# Hardwiring.net
KiCad netlist of a schematic drawn in Altium Designer
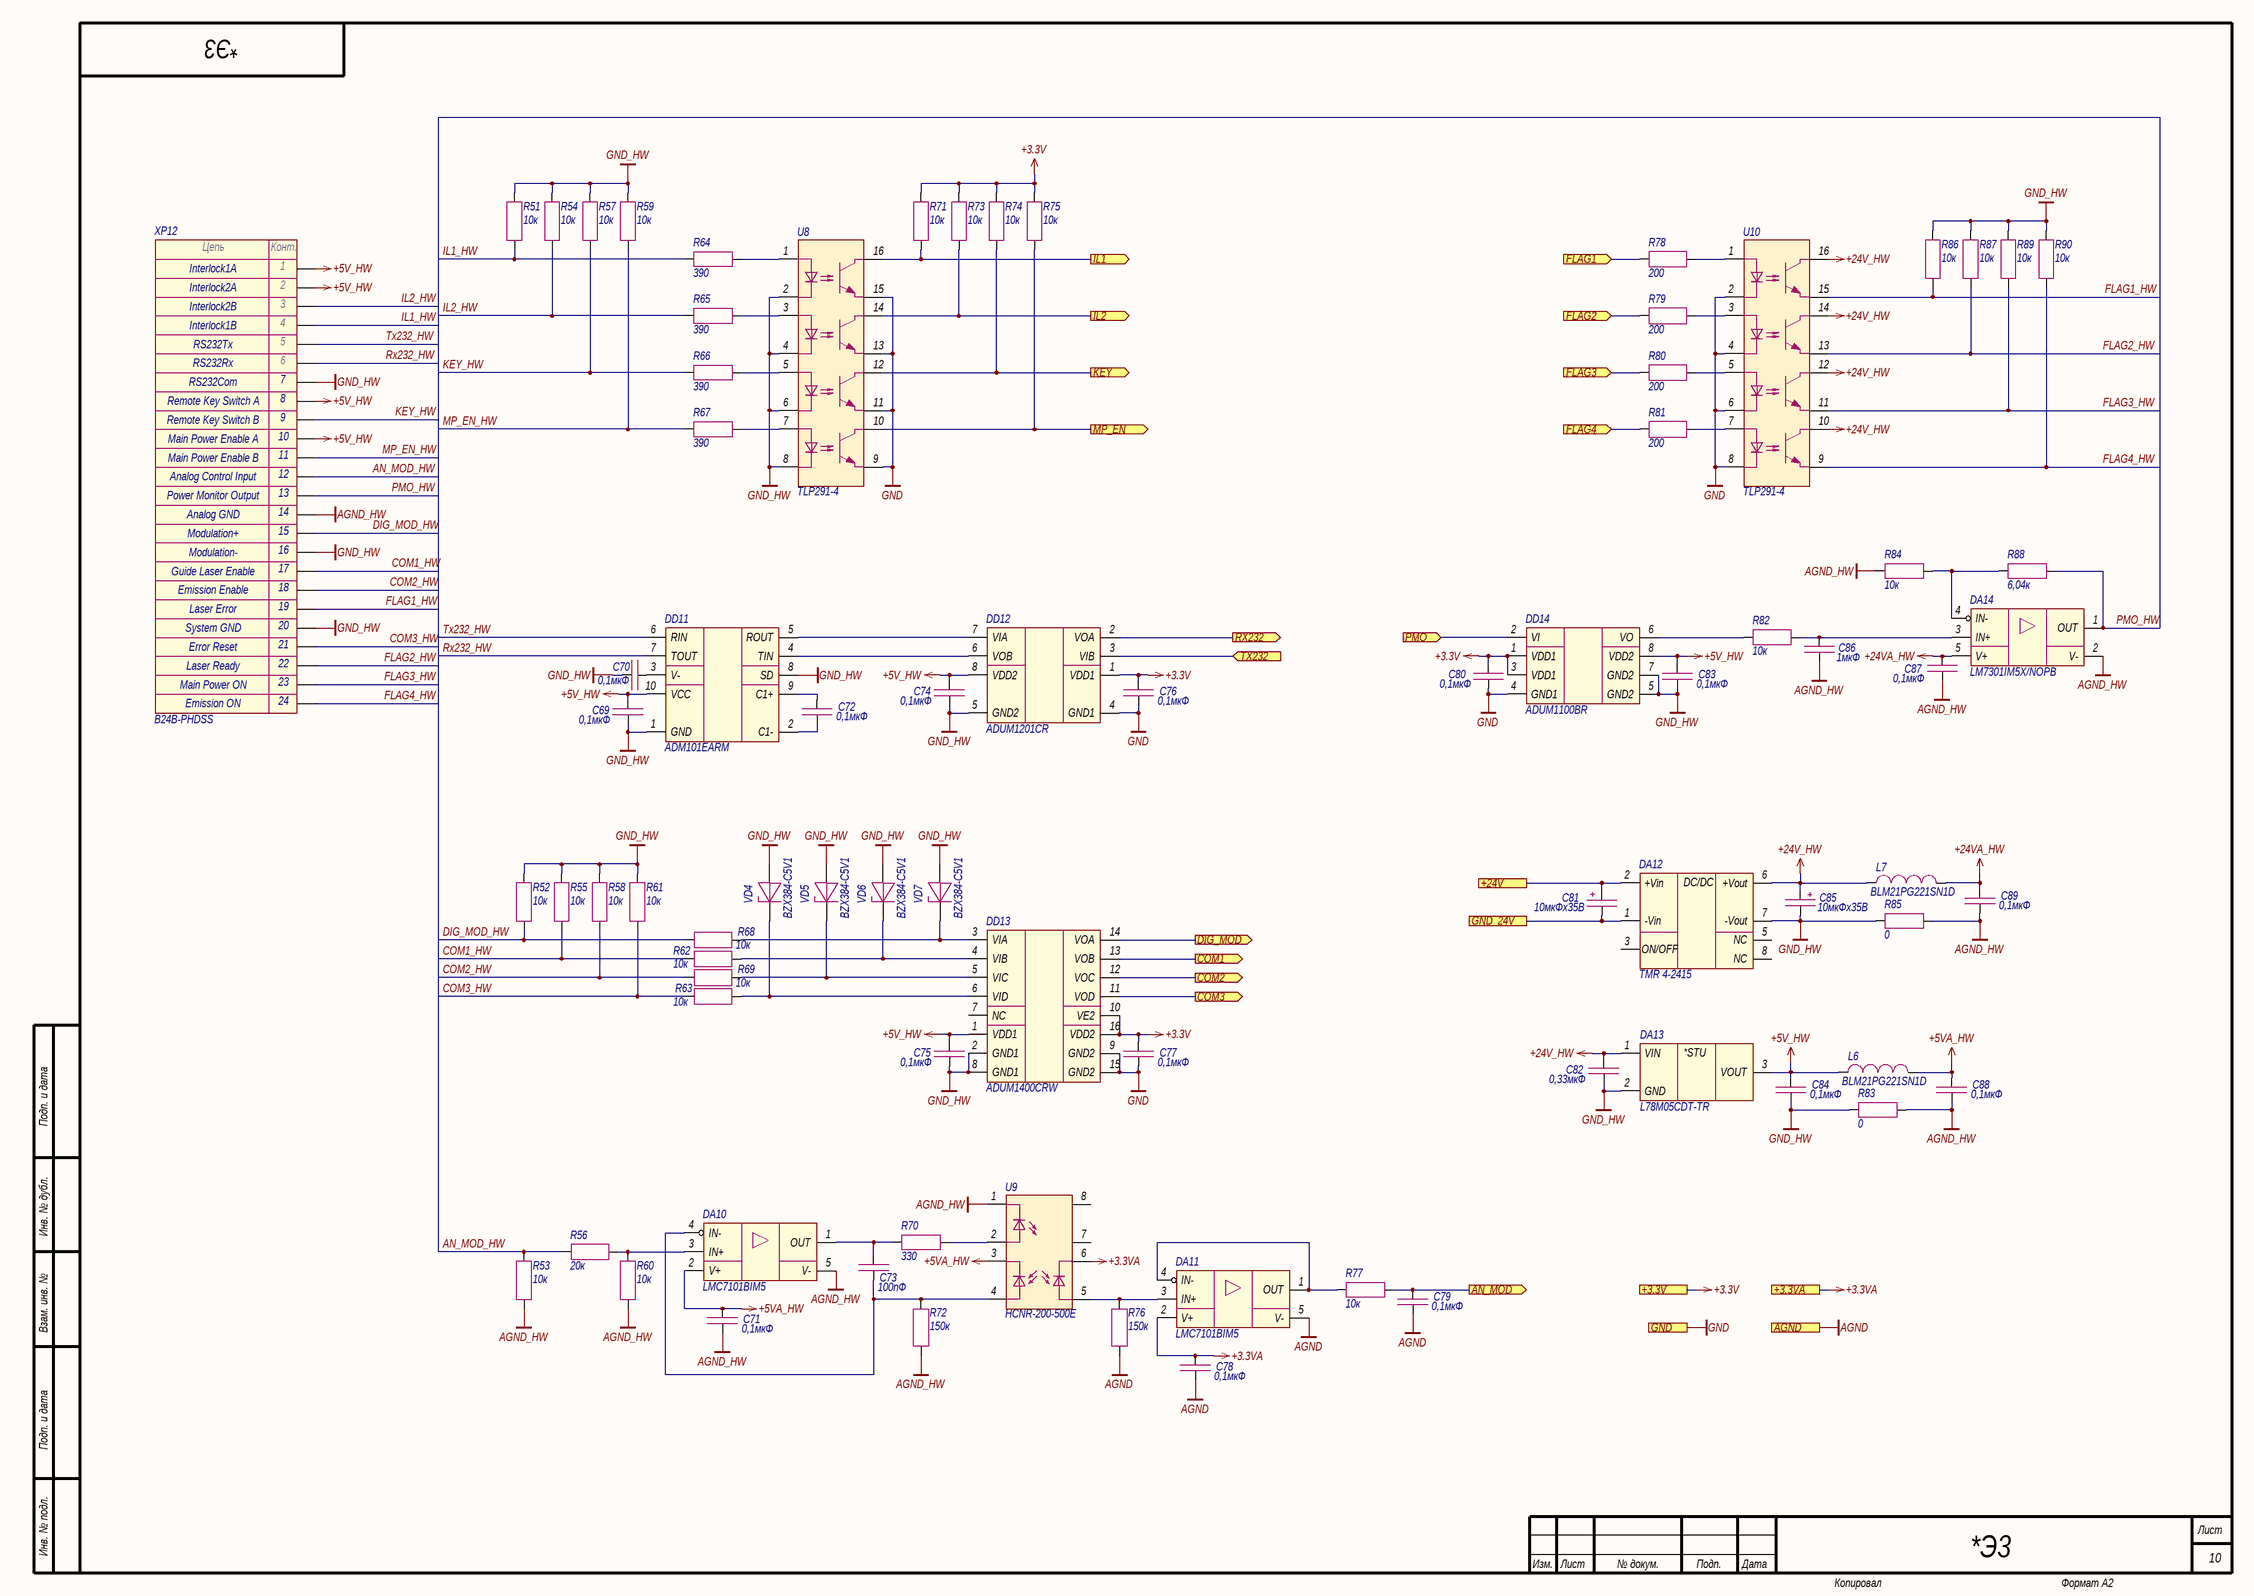
[diagram p0: Hardwiring.SchDoc]

(export (version "E")
  (design (tool "Eeschema 10.0.6"))
  (components
    (comp (ref "C69")
      (value "0,1мкФ")
      (footprint "Pcb_library:CAP_0603")
      (fields (field (name "MANUFACTURER") "Murata"))
      (libsource (lib "Schem_library") (part "Capacitor"))
    )
    (comp (ref "C70")
      (value "0,1мкФ")
      (footprint "Pcb_library:CAP_0603")
      (fields (field (name "MANUFACTURER") "Murata"))
      (libsource (lib "Schem_library") (part "Capacitor"))
    )
    (comp (ref "C71")
      (value "0,1мкФ")
      (footprint "Pcb_library:CAP_0603")
      (fields (field (name "MANUFACTURER") "Murata"))
      (libsource (lib "Schem_library") (part "Capacitor"))
    )
    (comp (ref "C72")
      (value "0,1мкФ")
      (footprint "Pcb_library:CAP_0603")
      (fields (field (name "MANUFACTURER") "Murata"))
      (libsource (lib "Schem_library") (part "Capacitor"))
    )
    (comp (ref "C73")
      (value "100пФ")
      (footprint "Pcb_library:CAP_0603")
      (fields (field (name "MANUFACTURER") "Murata"))
      (libsource (lib "Schem_library") (part "Capacitor"))
    )
    (comp (ref "C74")
      (value "0,1мкФ")
      (footprint "Pcb_library:CAP_0603")
      (fields (field (name "MANUFACTURER") "Murata"))
      (libsource (lib "Schem_library") (part "Capacitor"))
    )
    (comp (ref "C75")
      (value "0,1мкФ")
      (footprint "Pcb_library:CAP_0603")
      (fields (field (name "MANUFACTURER") "Murata"))
      (libsource (lib "Schem_library") (part "Capacitor"))
    )
    (comp (ref "C76")
      (value "0,1мкФ")
      (footprint "Pcb_library:CAP_0603")
      (fields (field (name "MANUFACTURER") "Murata"))
      (libsource (lib "Schem_library") (part "Capacitor"))
    )
    (comp (ref "C77")
      (value "0,1мкФ")
      (footprint "Pcb_library:CAP_0603")
      (fields (field (name "MANUFACTURER") "Murata"))
      (libsource (lib "Schem_library") (part "Capacitor"))
    )
    (comp (ref "C78")
      (value "0,1мкФ")
      (footprint "Pcb_library:CAP_0603")
      (fields (field (name "MANUFACTURER") "Murata"))
      (libsource (lib "Schem_library") (part "Capacitor"))
    )
    (comp (ref "C79")
      (value "0,1мкФ")
      (footprint "Pcb_library:CAP_0603")
      (fields (field (name "MANUFACTURER") "Murata"))
      (libsource (lib "Schem_library") (part "Capacitor"))
    )
    (comp (ref "C80")
      (value "0,1мкФ")
      (footprint "Pcb_library:CAP_0603")
      (fields (field (name "MANUFACTURER") "Murata"))
      (libsource (lib "Schem_library") (part "Capacitor"))
    )
    (comp (ref "C81")
      (value "10мкФх35B")
      (footprint "Pcb_library:CAP_C")
      (libsource (lib "Schem_library") (part "Capacitor_Polar"))
    )
    (comp (ref "C82")
      (value "0,33мкФ")
      (footprint "Pcb_library:CAP_0805")
      (fields (field (name "MANUFACTURER") "Murata"))
      (libsource (lib "Schem_library") (part "Capacitor"))
    )
    (comp (ref "C83")
      (value "0,1мкФ")
      (footprint "Pcb_library:CAP_0603")
      (fields (field (name "MANUFACTURER") "Murata"))
      (libsource (lib "Schem_library") (part "Capacitor"))
    )
    (comp (ref "C84")
      (value "0,1мкФ")
      (footprint "Pcb_library:CAP_0603")
      (fields (field (name "MANUFACTURER") "Murata"))
      (libsource (lib "Schem_library") (part "Capacitor"))
    )
    (comp (ref "C85")
      (value "10мкФх35B")
      (footprint "Pcb_library:CAP_C")
      (libsource (lib "Schem_library") (part "Capacitor_Polar"))
    )
    (comp (ref "C86")
      (value "1мкФ")
      (footprint "Pcb_library:CAP_0603")
      (fields (field (name "MANUFACTURER") "Murata"))
      (libsource (lib "Schem_library") (part "Capacitor"))
    )
    (comp (ref "C87")
      (value "0,1мкФ")
      (footprint "Pcb_library:CAP_0603")
      (fields (field (name "MANUFACTURER") "Murata"))
      (libsource (lib "Schem_library") (part "Capacitor"))
    )
    (comp (ref "C88")
      (value "0,1мкФ")
      (footprint "Pcb_library:CAP_0603")
      (fields (field (name "MANUFACTURER") "Murata"))
      (libsource (lib "Schem_library") (part "Capacitor"))
    )
    (comp (ref "C89")
      (value "0,1мкФ")
      (footprint "Pcb_library:CAP_0603")
      (fields (field (name "MANUFACTURER") "Murata"))
      (libsource (lib "Schem_library") (part "Capacitor"))
    )
    (comp (ref "DA10")
      (value "LMC7101BIM5")
      (footprint "Pcb_library:SOT-23-5")
      (fields (field (name "MANUFACTURER") "Texas Instruments"))
      (libsource (lib "Schem_library") (part "LMC7101"))
    )
    (comp (ref "DA11")
      (value "LMC7101BIM5")
      (footprint "Pcb_library:SOT-23-5")
      (fields (field (name "MANUFACTURER") "Texas Instruments"))
      (libsource (lib "Schem_library") (part "LMC7101"))
    )
    (comp (ref "DA12")
      (value "TMR 4-2415")
      (footprint "Pcb_library:TMR4 (SIP-8)")
      (fields (field (name "MANUFACTURER") "Traco Power"))
      (libsource (lib "Schem_library") (part "TMR4"))
    )
    (comp (ref "DA13")
      (value "L78M05CDT-TR")
      (footprint "Pcb_library:TO-252")
      (fields (field (name "MANUFACTURER") "STMicroelectronics"))
      (libsource (lib "Schem_library") (part "L78M"))
    )
    (comp (ref "DA14")
      (value "LM7301IM5X/NOPB")
      (footprint "Pcb_library:SOT-23-5")
      (fields (field (name "MANUFACTURER") "Texas Instruments"))
      (libsource (lib "Schem_library") (part "LM7301IM5"))
    )
    (comp (ref "DD11")
      (value "ADM101EARM")
      (footprint "Pcb_library:MSOP-10")
      (fields (field (name "MANUFACTURER") "Analog Devices"))
      (libsource (lib "Schem_library") (part "ADM101EARM"))
    )
    (comp (ref "DD12")
      (value "ADUM1201CR")
      (footprint "Pcb_library:SOIC-8")
      (fields (field (name "MANUFACTURER") "Analog Devices"))
      (libsource (lib "Schem_library") (part "ADUM1201"))
    )
    (comp (ref "DD13")
      (value "ADUM1400CRW")
      (footprint "Pcb_library:SOIC-16W")
      (fields (field (name "MANUFACTURER") "Analog Devices"))
      (libsource (lib "Schem_library") (part "ADUM1400"))
    )
    (comp (ref "DD14")
      (value "ADUM1100BR")
      (footprint "Pcb_library:SOIC-8")
      (fields (field (name "MANUFACTURER") "Analog Devices"))
      (libsource (lib "Schem_library") (part "ADUM1100"))
    )
    (comp (ref "L6")
      (value "BLM21PG221SN1D")
      (footprint "Pcb_library:IND_0805")
      (fields (field (name "MANUFACTURER") "Murata"))
      (libsource (lib "Schem_library") (part "Inductor"))
    )
    (comp (ref "L7")
      (value "BLM21PG221SN1D")
      (footprint "Pcb_library:IND_0805")
      (fields (field (name "MANUFACTURER") "Murata"))
      (libsource (lib "Schem_library") (part "Inductor"))
    )
    (comp (ref "R51")
      (value "10к")
      (footprint "Pcb_library:RES_0603")
      (fields (field (name "MANUFACTURER") "Yageo"))
      (libsource (lib "Schem_library") (part "Resistor"))
    )
    (comp (ref "R52")
      (value "10к")
      (footprint "Pcb_library:RES_0603")
      (fields (field (name "MANUFACTURER") "Yageo"))
      (libsource (lib "Schem_library") (part "Resistor"))
    )
    (comp (ref "R53")
      (value "10к")
      (footprint "Pcb_library:RES_0603")
      (fields (field (name "MANUFACTURER") "Yageo"))
      (libsource (lib "Schem_library") (part "Resistor"))
    )
    (comp (ref "R54")
      (value "10к")
      (footprint "Pcb_library:RES_0603")
      (fields (field (name "MANUFACTURER") "Yageo"))
      (libsource (lib "Schem_library") (part "Resistor"))
    )
    (comp (ref "R55")
      (value "10к")
      (footprint "Pcb_library:RES_0603")
      (fields (field (name "MANUFACTURER") "Yageo"))
      (libsource (lib "Schem_library") (part "Resistor"))
    )
    (comp (ref "R56")
      (value "20к")
      (footprint "Pcb_library:RES_0603")
      (fields (field (name "MANUFACTURER") "Yageo"))
      (libsource (lib "Schem_library") (part "Resistor"))
    )
    (comp (ref "R57")
      (value "10к")
      (footprint "Pcb_library:RES_0603")
      (fields (field (name "MANUFACTURER") "Yageo"))
      (libsource (lib "Schem_library") (part "Resistor"))
    )
    (comp (ref "R58")
      (value "10к")
      (footprint "Pcb_library:RES_0603")
      (fields (field (name "MANUFACTURER") "Yageo"))
      (libsource (lib "Schem_library") (part "Resistor"))
    )
    (comp (ref "R59")
      (value "10к")
      (footprint "Pcb_library:RES_0603")
      (fields (field (name "MANUFACTURER") "Yageo"))
      (libsource (lib "Schem_library") (part "Resistor"))
    )
    (comp (ref "R60")
      (value "10к")
      (footprint "Pcb_library:RES_0603")
      (fields (field (name "MANUFACTURER") "Yageo"))
      (libsource (lib "Schem_library") (part "Resistor"))
    )
    (comp (ref "R61")
      (value "10к")
      (footprint "Pcb_library:RES_0603")
      (fields (field (name "MANUFACTURER") "Yageo"))
      (libsource (lib "Schem_library") (part "Resistor"))
    )
    (comp (ref "R62")
      (value "10к")
      (footprint "Pcb_library:RES_0603")
      (fields (field (name "MANUFACTURER") "Yageo"))
      (libsource (lib "Schem_library") (part "Resistor"))
    )
    (comp (ref "R63")
      (value "10к")
      (footprint "Pcb_library:RES_0603")
      (fields (field (name "MANUFACTURER") "Yageo"))
      (libsource (lib "Schem_library") (part "Resistor"))
    )
    (comp (ref "R64")
      (value "390")
      (footprint "Pcb_library:RES_0603")
      (fields (field (name "MANUFACTURER") "Yageo"))
      (libsource (lib "Schem_library") (part "Resistor"))
    )
    (comp (ref "R65")
      (value "390")
      (footprint "Pcb_library:RES_0603")
      (fields (field (name "MANUFACTURER") "Yageo"))
      (libsource (lib "Schem_library") (part "Resistor"))
    )
    (comp (ref "R66")
      (value "390")
      (footprint "Pcb_library:RES_0603")
      (fields (field (name "MANUFACTURER") "Yageo"))
      (libsource (lib "Schem_library") (part "Resistor"))
    )
    (comp (ref "R67")
      (value "390")
      (footprint "Pcb_library:RES_0603")
      (fields (field (name "MANUFACTURER") "Yageo"))
      (libsource (lib "Schem_library") (part "Resistor"))
    )
    (comp (ref "R68")
      (value "10к")
      (footprint "Pcb_library:RES_0603")
      (fields (field (name "MANUFACTURER") "Yageo"))
      (libsource (lib "Schem_library") (part "Resistor"))
    )
    (comp (ref "R69")
      (value "10к")
      (footprint "Pcb_library:RES_0603")
      (fields (field (name "MANUFACTURER") "Yageo"))
      (libsource (lib "Schem_library") (part "Resistor"))
    )
    (comp (ref "R70")
      (value "330")
      (footprint "Pcb_library:RES_0603")
      (fields (field (name "MANUFACTURER") "Yageo"))
      (libsource (lib "Schem_library") (part "Resistor"))
    )
    (comp (ref "R71")
      (value "10к")
      (footprint "Pcb_library:RES_0603")
      (fields (field (name "MANUFACTURER") "Yageo"))
      (libsource (lib "Schem_library") (part "Resistor"))
    )
    (comp (ref "R72")
      (value "150к")
      (footprint "Pcb_library:RES_0603")
      (fields (field (name "MANUFACTURER") "Yageo"))
      (libsource (lib "Schem_library") (part "Resistor"))
    )
    (comp (ref "R73")
      (value "10к")
      (footprint "Pcb_library:RES_0603")
      (fields (field (name "MANUFACTURER") "Yageo"))
      (libsource (lib "Schem_library") (part "Resistor"))
    )
    (comp (ref "R74")
      (value "10к")
      (footprint "Pcb_library:RES_0603")
      (fields (field (name "MANUFACTURER") "Yageo"))
      (libsource (lib "Schem_library") (part "Resistor"))
    )
    (comp (ref "R75")
      (value "10к")
      (footprint "Pcb_library:RES_0603")
      (fields (field (name "MANUFACTURER") "Yageo"))
      (libsource (lib "Schem_library") (part "Resistor"))
    )
    (comp (ref "R76")
      (value "150к")
      (footprint "Pcb_library:RES_0603")
      (fields (field (name "MANUFACTURER") "Yageo"))
      (libsource (lib "Schem_library") (part "Resistor"))
    )
    (comp (ref "R77")
      (value "10к")
      (footprint "Pcb_library:RES_0603")
      (fields (field (name "MANUFACTURER") "Yageo"))
      (libsource (lib "Schem_library") (part "Resistor"))
    )
    (comp (ref "R78")
      (value "200")
      (footprint "Pcb_library:RES_0603")
      (fields (field (name "MANUFACTURER") "Yageo"))
      (libsource (lib "Schem_library") (part "Resistor"))
    )
    (comp (ref "R79")
      (value "200")
      (footprint "Pcb_library:RES_0603")
      (fields (field (name "MANUFACTURER") "Yageo"))
      (libsource (lib "Schem_library") (part "Resistor"))
    )
    (comp (ref "R80")
      (value "200")
      (footprint "Pcb_library:RES_0603")
      (fields (field (name "MANUFACTURER") "Yageo"))
      (libsource (lib "Schem_library") (part "Resistor"))
    )
    (comp (ref "R81")
      (value "200")
      (footprint "Pcb_library:RES_0603")
      (fields (field (name "MANUFACTURER") "Yageo"))
      (libsource (lib "Schem_library") (part "Resistor"))
    )
    (comp (ref "R82")
      (value "10к")
      (footprint "Pcb_library:RES_0603")
      (fields (field (name "MANUFACTURER") "Yageo"))
      (libsource (lib "Schem_library") (part "Resistor"))
    )
    (comp (ref "R83")
      (value "0")
      (footprint "Pcb_library:RES_0805")
      (fields (field (name "MANUFACTURER") "Yageo"))
      (libsource (lib "Schem_library") (part "Resistor"))
    )
    (comp (ref "R84")
      (value "10к")
      (footprint "Pcb_library:RES_0603")
      (fields (field (name "MANUFACTURER") "Yageo"))
      (libsource (lib "Schem_library") (part "Resistor"))
    )
    (comp (ref "R85")
      (value "0")
      (footprint "Pcb_library:RES_0805")
      (fields (field (name "MANUFACTURER") "Yageo"))
      (libsource (lib "Schem_library") (part "Resistor"))
    )
    (comp (ref "R86")
      (value "10к")
      (footprint "Pcb_library:RES_0603")
      (fields (field (name "MANUFACTURER") "Yageo"))
      (libsource (lib "Schem_library") (part "Resistor"))
    )
    (comp (ref "R87")
      (value "10к")
      (footprint "Pcb_library:RES_0603")
      (fields (field (name "MANUFACTURER") "Yageo"))
      (libsource (lib "Schem_library") (part "Resistor"))
    )
    (comp (ref "R88")
      (value "6,04к")
      (footprint "Pcb_library:RES_0603")
      (fields (field (name "MANUFACTURER") "Yageo"))
      (libsource (lib "Schem_library") (part "Resistor"))
    )
    (comp (ref "R89")
      (value "10к")
      (footprint "Pcb_library:RES_0603")
      (fields (field (name "MANUFACTURER") "Yageo"))
      (libsource (lib "Schem_library") (part "Resistor"))
    )
    (comp (ref "R90")
      (value "10к")
      (footprint "Pcb_library:RES_0603")
      (fields (field (name "MANUFACTURER") "Yageo"))
      (libsource (lib "Schem_library") (part "Resistor"))
    )
    (comp (ref "U8")
      (value "TLP291-4")
      (footprint "Pcb_library:SOP-16")
      (fields (field (name "MANUFACTURER") "Toshiba"))
      (libsource (lib "Schem_library") (part "TLP281-4"))
    )
    (comp (ref "U9")
      (value "HCNR-200-500E")
      (footprint "Pcb_library:HCNR200")
      (fields (field (name "MANUFACTURER") "Avago"))
      (libsource (lib "Schem_library") (part "HCNR200"))
    )
    (comp (ref "U10")
      (value "TLP291-4")
      (footprint "Pcb_library:SOP-16")
      (fields (field (name "MANUFACTURER") "Toshiba"))
      (libsource (lib "Schem_library") (part "TLP281-4"))
    )
    (comp (ref "VD4")
      (value "BZX384-C5V1")
      (footprint "Pcb_library:SOD-323")
      (fields (field (name "MANUFACTURER") "Nexperia"))
      (libsource (lib "Schem_library") (part "Diode_Zener"))
    )
    (comp (ref "VD5")
      (value "BZX384-C5V1")
      (footprint "Pcb_library:SOD-323")
      (fields (field (name "MANUFACTURER") "Nexperia"))
      (libsource (lib "Schem_library") (part "Diode_Zener"))
    )
    (comp (ref "VD6")
      (value "BZX384-C5V1")
      (footprint "Pcb_library:SOD-323")
      (fields (field (name "MANUFACTURER") "Nexperia"))
      (libsource (lib "Schem_library") (part "Diode_Zener"))
    )
    (comp (ref "VD7")
      (value "BZX384-C5V1")
      (footprint "Pcb_library:SOD-323")
      (fields (field (name "MANUFACTURER") "Nexperia"))
      (libsource (lib "Schem_library") (part "Diode_Zener"))
    )
    (comp (ref "XP12")
      (value "B24B-PHDSS")
      (footprint "Pcb_library:B24B-PHDSS")
      (fields (field (name "MANUFACTURER") "JST"))
      (libsource (lib "Schem_library") (part "Connector-24"))
    )
  )
  (nets
    (net (code "1") (name "+3.3V") (class "Default")
      (node (ref "C76") (pin "1") (pinfunction "1_1") (pintype "passive"))
      (node (ref "C77") (pin "1") (pinfunction "1_1") (pintype "passive"))
      (node (ref "C80") (pin "1") (pinfunction "1_1") (pintype "passive"))
      (node (ref "DD12") (pin "1") (pinfunction "VDD1_1") (pintype "passive"))
      (node (ref "DD13") (pin "10") (pinfunction "VE2_10") (pintype "passive"))
      (node (ref "DD13") (pin "16") (pinfunction "VDD2_16") (pintype "passive"))
      (node (ref "DD14") (pin "1") (pinfunction "VDD1_1") (pintype "passive"))
      (node (ref "DD14") (pin "3") (pinfunction "VDD1_3") (pintype "passive"))
      (node (ref "R71") (pin "1") (pinfunction "1_1") (pintype "passive"))
      (node (ref "R73") (pin "1") (pinfunction "1_1") (pintype "passive"))
      (node (ref "R74") (pin "1") (pinfunction "1_1") (pintype "passive"))
      (node (ref "R75") (pin "1") (pinfunction "1_1") (pintype "passive"))
    )
    (net (code "2") (name "+3.3VA") (class "Default")
      (node (ref "C78") (pin "1") (pinfunction "1_1") (pintype "passive"))
      (node (ref "DA11") (pin "2") (pinfunction "V+_2") (pintype "passive"))
      (node (ref "U9") (pin "6") (pintype "passive"))
    )
    (net (code "3") (name "+5VA_HW") (class "Default")
      (node (ref "C71") (pin "1") (pinfunction "1_1") (pintype "passive"))
      (node (ref "C88") (pin "1") (pinfunction "1_1") (pintype "passive"))
      (node (ref "DA10") (pin "2") (pinfunction "V+_2") (pintype "passive"))
      (node (ref "L6") (pin "2") (pinfunction "2_2") (pintype "passive"))
      (node (ref "U9") (pin "3") (pintype "passive"))
    )
    (net (code "4") (name "+5V_HW") (class "Default")
      (node (ref "C69") (pin "1") (pinfunction "1_1") (pintype "passive"))
      (node (ref "C74") (pin "1") (pinfunction "1_1") (pintype "passive"))
      (node (ref "C75") (pin "1") (pinfunction "1_1") (pintype "passive"))
      (node (ref "C83") (pin "1") (pinfunction "1_1") (pintype "passive"))
      (node (ref "C84") (pin "1") (pinfunction "1_1") (pintype "passive"))
      (node (ref "DA13") (pin "3") (pinfunction "VOUT_3") (pintype "passive"))
      (node (ref "DD11") (pin "10") (pinfunction "VCC_10") (pintype "passive"))
      (node (ref "DD12") (pin "8") (pinfunction "VDD2_8") (pintype "passive"))
      (node (ref "DD13") (pin "1") (pinfunction "VDD1_1") (pintype "passive"))
      (node (ref "DD14") (pin "8") (pinfunction "VDD2_8") (pintype "passive"))
      (node (ref "L6") (pin "1") (pinfunction "1_1") (pintype "passive"))
      (node (ref "XP12") (pin "1") (pintype "passive"))
      (node (ref "XP12") (pin "10") (pintype "passive"))
      (node (ref "XP12") (pin "2") (pintype "passive"))
      (node (ref "XP12") (pin "8") (pintype "passive"))
    )
    (net (code "5") (name "+24VA_HW") (class "Default")
      (node (ref "C87") (pin "1") (pinfunction "1_1") (pintype "passive"))
      (node (ref "C89") (pin "1") (pinfunction "1_1") (pintype "passive"))
      (node (ref "DA14") (pin "5") (pinfunction "V+_5") (pintype "passive"))
      (node (ref "L7") (pin "2") (pinfunction "2_2") (pintype "passive"))
    )
    (net (code "6") (name "+24V_HW") (class "Default")
      (node (ref "C82") (pin "2") (pinfunction "2_2") (pintype "passive"))
      (node (ref "C85") (pin "1") (pinfunction "1_1") (pintype "passive"))
      (node (ref "DA12") (pin "6") (pinfunction "+Vout_6") (pintype "passive"))
      (node (ref "DA13") (pin "1") (pinfunction "VIN_1") (pintype "passive"))
      (node (ref "L7") (pin "1") (pinfunction "1_1") (pintype "passive"))
      (node (ref "U10") (pin "10") (pintype "passive"))
      (node (ref "U10") (pin "12") (pintype "passive"))
      (node (ref "U10") (pin "14") (pintype "passive"))
      (node (ref "U10") (pin "16") (pintype "passive"))
    )
    (net (code "7") (name "/+24V") (class "Default")
      (node (ref "C81") (pin "1") (pinfunction "1_1") (pintype "passive"))
      (node (ref "DA12") (pin "2") (pinfunction "+Vin_2") (pintype "passive"))
    )
    (net (code "8") (name "/AN_MOD") (class "Default")
      (node (ref "C79") (pin "1") (pinfunction "1_1") (pintype "passive"))
      (node (ref "R77") (pin "2") (pinfunction "2_2") (pintype "passive"))
    )
    (net (code "9") (name "/AN_MOD_HW") (class "Default")
      (node (ref "R53") (pin "1") (pinfunction "1_1") (pintype "passive"))
      (node (ref "R56") (pin "1") (pinfunction "1_1") (pintype "passive"))
      (node (ref "XP12") (pin "12") (pintype "passive"))
    )
    (net (code "10") (name "/COM1") (class "Default")
      (node (ref "DD13") (pin "13") (pinfunction "VOB_13") (pintype "passive"))
    )
    (net (code "11") (name "/COM1_HW") (class "Default")
      (node (ref "R55") (pin "2") (pinfunction "2_2") (pintype "passive"))
      (node (ref "R62") (pin "1") (pinfunction "1_1") (pintype "passive"))
      (node (ref "XP12") (pin "17") (pintype "passive"))
    )
    (net (code "12") (name "/COM2") (class "Default")
      (node (ref "DD13") (pin "12") (pinfunction "VOC_12") (pintype "passive"))
    )
    (net (code "13") (name "/COM2_HW") (class "Default")
      (node (ref "R58") (pin "2") (pinfunction "2_2") (pintype "passive"))
      (node (ref "R69") (pin "1") (pinfunction "1_1") (pintype "passive"))
      (node (ref "XP12") (pin "18") (pintype "passive"))
    )
    (net (code "14") (name "/COM3") (class "Default")
      (node (ref "DD13") (pin "11") (pinfunction "VOD_11") (pintype "passive"))
    )
    (net (code "15") (name "/COM3_HW") (class "Default")
      (node (ref "R61") (pin "2") (pinfunction "2_2") (pintype "passive"))
      (node (ref "R63") (pin "1") (pinfunction "1_1") (pintype "passive"))
      (node (ref "XP12") (pin "21") (pintype "passive"))
    )
    (net (code "16") (name "/DIG_MOD") (class "Default")
      (node (ref "DD13") (pin "14") (pinfunction "VOA_14") (pintype "passive"))
    )
    (net (code "17") (name "/DIG_MOD_HW") (class "Default")
      (node (ref "R52") (pin "2") (pinfunction "2_2") (pintype "passive"))
      (node (ref "R68") (pin "1") (pinfunction "1_1") (pintype "passive"))
      (node (ref "XP12") (pin "15") (pintype "passive"))
    )
    (net (code "18") (name "/FLAG1") (class "Default")
      (node (ref "R78") (pin "2") (pinfunction "2_2") (pintype "passive"))
    )
    (net (code "19") (name "/FLAG1_HW") (class "Default")
      (node (ref "R86") (pin "2") (pinfunction "2_2") (pintype "passive"))
      (node (ref "U10") (pin "15") (pintype "passive"))
      (node (ref "XP12") (pin "19") (pintype "passive"))
    )
    (net (code "20") (name "/FLAG2") (class "Default")
      (node (ref "R79") (pin "2") (pinfunction "2_2") (pintype "passive"))
    )
    (net (code "21") (name "/FLAG2_HW") (class "Default")
      (node (ref "R87") (pin "2") (pinfunction "2_2") (pintype "passive"))
      (node (ref "U10") (pin "13") (pintype "passive"))
      (node (ref "XP12") (pin "22") (pintype "passive"))
    )
    (net (code "22") (name "/FLAG3") (class "Default")
      (node (ref "R80") (pin "2") (pinfunction "2_2") (pintype "passive"))
    )
    (net (code "23") (name "/FLAG3_HW") (class "Default")
      (node (ref "R89") (pin "2") (pinfunction "2_2") (pintype "passive"))
      (node (ref "U10") (pin "11") (pintype "passive"))
      (node (ref "XP12") (pin "23") (pintype "passive"))
    )
    (net (code "24") (name "/FLAG4") (class "Default")
      (node (ref "R81") (pin "2") (pinfunction "2_2") (pintype "passive"))
    )
    (net (code "25") (name "/FLAG4_HW") (class "Default")
      (node (ref "R90") (pin "2") (pinfunction "2_2") (pintype "passive"))
      (node (ref "U10") (pin "9") (pintype "passive"))
      (node (ref "XP12") (pin "24") (pintype "passive"))
    )
    (net (code "26") (name "/GND_24V") (class "Default")
      (node (ref "C81") (pin "2") (pinfunction "2_2") (pintype "passive"))
      (node (ref "DA12") (pin "1") (pinfunction "-Vin_1") (pintype "passive"))
    )
    (net (code "27") (name "/IL1") (class "Default")
      (node (ref "R71") (pin "2") (pinfunction "2_2") (pintype "passive"))
      (node (ref "U8") (pin "16") (pintype "passive"))
    )
    (net (code "28") (name "/IL1_HW") (class "Default")
      (node (ref "R51") (pin "2") (pinfunction "2_2") (pintype "passive"))
      (node (ref "R64") (pin "1") (pinfunction "1_1") (pintype "passive"))
      (node (ref "XP12") (pin "4") (pintype "passive"))
    )
    (net (code "29") (name "/IL2") (class "Default")
      (node (ref "R73") (pin "2") (pinfunction "2_2") (pintype "passive"))
      (node (ref "U8") (pin "14") (pintype "passive"))
    )
    (net (code "30") (name "/IL2_HW") (class "Default")
      (node (ref "R54") (pin "2") (pinfunction "2_2") (pintype "passive"))
      (node (ref "R65") (pin "1") (pinfunction "1_1") (pintype "passive"))
      (node (ref "XP12") (pin "3") (pintype "passive"))
    )
    (net (code "31") (name "/KEY") (class "Default")
      (node (ref "R74") (pin "2") (pinfunction "2_2") (pintype "passive"))
      (node (ref "U8") (pin "12") (pintype "passive"))
    )
    (net (code "32") (name "/KEY_HW") (class "Default")
      (node (ref "R57") (pin "2") (pinfunction "2_2") (pintype "passive"))
      (node (ref "R66") (pin "1") (pinfunction "1_1") (pintype "passive"))
      (node (ref "XP12") (pin "9") (pintype "passive"))
    )
    (net (code "33") (name "/MP_EN") (class "Default")
      (node (ref "R75") (pin "2") (pinfunction "2_2") (pintype "passive"))
      (node (ref "U8") (pin "10") (pintype "passive"))
    )
    (net (code "34") (name "/MP_EN_HW") (class "Default")
      (node (ref "R59") (pin "2") (pinfunction "2_2") (pintype "passive"))
      (node (ref "R67") (pin "1") (pinfunction "1_1") (pintype "passive"))
      (node (ref "XP12") (pin "11") (pintype "passive"))
    )
    (net (code "35") (name "/PMO") (class "Default")
      (node (ref "DD14") (pin "2") (pinfunction "VI_2") (pintype "passive"))
    )
    (net (code "36") (name "/PMO_HW") (class "Default")
      (node (ref "DA14") (pin "1") (pinfunction "OUT_1") (pintype "passive"))
      (node (ref "R88") (pin "2") (pinfunction "2_2") (pintype "passive"))
      (node (ref "XP12") (pin "13") (pintype "passive"))
    )
    (net (code "37") (name "/RX232") (class "Default")
      (node (ref "DD12") (pin "2") (pinfunction "VOA_2") (pintype "passive"))
    )
    (net (code "38") (name "/Rx232_HW") (class "Default")
      (node (ref "DD11") (pin "7") (pinfunction "TOUT_7") (pintype "passive"))
      (node (ref "XP12") (pin "6") (pintype "passive"))
    )
    (net (code "39") (name "/TX232") (class "Default")
      (node (ref "DD12") (pin "3") (pinfunction "VIB_3") (pintype "passive"))
    )
    (net (code "40") (name "/Tx232_HW") (class "Default")
      (node (ref "DD11") (pin "6") (pinfunction "RIN_6") (pintype "passive"))
      (node (ref "XP12") (pin "5") (pintype "passive"))
    )
    (net (code "41") (name "AGND") (class "Default")
      (node (ref "C78") (pin "2") (pinfunction "2_2") (pintype "passive"))
      (node (ref "C79") (pin "2") (pinfunction "2_2") (pintype "passive"))
      (node (ref "DA11") (pin "5") (pinfunction "V-_5") (pintype "passive"))
      (node (ref "R76") (pin "2") (pinfunction "2_2") (pintype "passive"))
    )
    (net (code "42") (name "AGND_HW") (class "Default")
      (node (ref "C71") (pin "2") (pinfunction "2_2") (pintype "passive"))
      (node (ref "C86") (pin "2") (pinfunction "2_2") (pintype "passive"))
      (node (ref "C87") (pin "2") (pinfunction "2_2") (pintype "passive"))
      (node (ref "C88") (pin "2") (pinfunction "2_2") (pintype "passive"))
      (node (ref "C89") (pin "2") (pinfunction "2_2") (pintype "passive"))
      (node (ref "DA10") (pin "5") (pinfunction "V-_5") (pintype "passive"))
      (node (ref "DA14") (pin "2") (pinfunction "V-_2") (pintype "passive"))
      (node (ref "R53") (pin "2") (pinfunction "2_2") (pintype "passive"))
      (node (ref "R60") (pin "2") (pinfunction "2_2") (pintype "passive"))
      (node (ref "R72") (pin "2") (pinfunction "2_2") (pintype "passive"))
      (node (ref "R83") (pin "2") (pinfunction "2_2") (pintype "passive"))
      (node (ref "R84") (pin "1") (pinfunction "1_1") (pintype "passive"))
      (node (ref "R85") (pin "2") (pinfunction "2_2") (pintype "passive"))
      (node (ref "U9") (pin "1") (pintype "passive"))
      (node (ref "XP12") (pin "14") (pintype "passive"))
    )
    (net (code "43") (name "GND") (class "Default")
      (node (ref "C76") (pin "2") (pinfunction "2_2") (pintype "passive"))
      (node (ref "C77") (pin "2") (pinfunction "2_2") (pintype "passive"))
      (node (ref "C80") (pin "2") (pinfunction "2_2") (pintype "passive"))
      (node (ref "DD12") (pin "4") (pinfunction "GND1_4") (pintype "passive"))
      (node (ref "DD13") (pin "15") (pinfunction "GND2_15") (pintype "passive"))
      (node (ref "DD13") (pin "9") (pinfunction "GND2_9") (pintype "passive"))
      (node (ref "DD14") (pin "4") (pinfunction "GND1_4") (pintype "passive"))
      (node (ref "U10") (pin "2") (pintype "passive"))
      (node (ref "U10") (pin "4") (pintype "passive"))
      (node (ref "U10") (pin "6") (pintype "passive"))
      (node (ref "U10") (pin "8") (pintype "passive"))
      (node (ref "U8") (pin "11") (pintype "passive"))
      (node (ref "U8") (pin "13") (pintype "passive"))
      (node (ref "U8") (pin "15") (pintype "passive"))
      (node (ref "U8") (pin "9") (pintype "passive"))
    )
    (net (code "44") (name "GND_HW") (class "Default")
      (node (ref "C69") (pin "2") (pinfunction "2_2") (pintype "passive"))
      (node (ref "C70") (pin "2") (pinfunction "2_2") (pintype "passive"))
      (node (ref "C74") (pin "2") (pinfunction "2_2") (pintype "passive"))
      (node (ref "C75") (pin "2") (pinfunction "2_2") (pintype "passive"))
      (node (ref "C82") (pin "1") (pinfunction "1_1") (pintype "passive"))
      (node (ref "C83") (pin "2") (pinfunction "2_2") (pintype "passive"))
      (node (ref "C84") (pin "2") (pinfunction "2_2") (pintype "passive"))
      (node (ref "C85") (pin "2") (pinfunction "2_2") (pintype "passive"))
      (node (ref "DA12") (pin "7") (pinfunction "-Vout_7") (pintype "passive"))
      (node (ref "DA13") (pin "2") (pinfunction "GND_2") (pintype "passive"))
      (node (ref "DD11") (pin "1") (pinfunction "GND_1") (pintype "passive"))
      (node (ref "DD11") (pin "8") (pinfunction "SD_8") (pintype "passive"))
      (node (ref "DD12") (pin "5") (pinfunction "GND2_5") (pintype "passive"))
      (node (ref "DD13") (pin "2") (pinfunction "GND1_2") (pintype "passive"))
      (node (ref "DD13") (pin "8") (pinfunction "GND1_8") (pintype "passive"))
      (node (ref "DD14") (pin "5") (pinfunction "GND2_5") (pintype "passive"))
      (node (ref "DD14") (pin "7") (pinfunction "GND2_7") (pintype "passive"))
      (node (ref "R51") (pin "1") (pinfunction "1_1") (pintype "passive"))
      (node (ref "R52") (pin "1") (pinfunction "1_1") (pintype "passive"))
      (node (ref "R54") (pin "1") (pinfunction "1_1") (pintype "passive"))
      (node (ref "R55") (pin "1") (pinfunction "1_1") (pintype "passive"))
      (node (ref "R57") (pin "1") (pinfunction "1_1") (pintype "passive"))
      (node (ref "R58") (pin "1") (pinfunction "1_1") (pintype "passive"))
      (node (ref "R59") (pin "1") (pinfunction "1_1") (pintype "passive"))
      (node (ref "R61") (pin "1") (pinfunction "1_1") (pintype "passive"))
      (node (ref "R83") (pin "1") (pinfunction "1_1") (pintype "passive"))
      (node (ref "R85") (pin "1") (pinfunction "1_1") (pintype "passive"))
      (node (ref "R86") (pin "1") (pinfunction "1_1") (pintype "passive"))
      (node (ref "R87") (pin "1") (pinfunction "1_1") (pintype "passive"))
      (node (ref "R89") (pin "1") (pinfunction "1_1") (pintype "passive"))
      (node (ref "R90") (pin "1") (pinfunction "1_1") (pintype "passive"))
      (node (ref "U8") (pin "2") (pintype "passive"))
      (node (ref "U8") (pin "4") (pintype "passive"))
      (node (ref "U8") (pin "6") (pintype "passive"))
      (node (ref "U8") (pin "8") (pintype "passive"))
      (node (ref "VD4") (pin "2") (pinfunction "A_2") (pintype "passive"))
      (node (ref "VD5") (pin "2") (pinfunction "A_2") (pintype "passive"))
      (node (ref "VD6") (pin "2") (pinfunction "A_2") (pintype "passive"))
      (node (ref "VD7") (pin "2") (pinfunction "A_2") (pintype "passive"))
      (node (ref "XP12") (pin "16") (pintype "passive"))
      (node (ref "XP12") (pin "20") (pintype "passive"))
      (node (ref "XP12") (pin "7") (pintype "passive"))
    )
    (net (code "45") (name "Net-(DA10-IN+)") (class "Default")
      (node (ref "DA10") (pin "3") (pinfunction "IN+_3") (pintype "passive"))
      (node (ref "R56") (pin "2") (pinfunction "2_2") (pintype "passive"))
      (node (ref "R60") (pin "1") (pinfunction "1_1") (pintype "passive"))
    )
    (net (code "46") (name "Net-(DA10-IN-)") (class "Default")
      (node (ref "C73") (pin "2") (pinfunction "2_2") (pintype "passive"))
      (node (ref "DA10") (pin "4") (pinfunction "IN-_4") (pintype "passive"))
      (node (ref "R72") (pin "1") (pinfunction "1_1") (pintype "passive"))
      (node (ref "U9") (pin "4") (pintype "passive"))
    )
    (net (code "47") (name "Net-(DA10-OUT)") (class "Default")
      (node (ref "C73") (pin "1") (pinfunction "1_1") (pintype "passive"))
      (node (ref "DA10") (pin "1") (pinfunction "OUT_1") (pintype "passive"))
      (node (ref "R70") (pin "1") (pinfunction "1_1") (pintype "passive"))
    )
    (net (code "48") (name "Net-(DA11-IN+)") (class "Default")
      (node (ref "DA11") (pin "3") (pinfunction "IN+_3") (pintype "passive"))
      (node (ref "R76") (pin "1") (pinfunction "1_1") (pintype "passive"))
      (node (ref "U9") (pin "5") (pintype "passive"))
    )
    (net (code "49") (name "Net-(DA11-IN-)") (class "Default")
      (node (ref "DA11") (pin "1") (pinfunction "OUT_1") (pintype "passive"))
      (node (ref "DA11") (pin "4") (pinfunction "IN-_4") (pintype "passive"))
      (node (ref "R77") (pin "1") (pinfunction "1_1") (pintype "passive"))
    )
    (net (code "50") (name "Net-(DA14-IN+)") (class "Default")
      (node (ref "C86") (pin "1") (pinfunction "1_1") (pintype "passive"))
      (node (ref "DA14") (pin "3") (pinfunction "IN+_3") (pintype "passive"))
      (node (ref "R82") (pin "2") (pinfunction "2_2") (pintype "passive"))
    )
    (net (code "51") (name "Net-(DA14-IN-)") (class "Default")
      (node (ref "DA14") (pin "4") (pinfunction "IN-_4") (pintype "passive"))
      (node (ref "R84") (pin "2") (pinfunction "2_2") (pintype "passive"))
      (node (ref "R88") (pin "1") (pinfunction "1_1") (pintype "passive"))
    )
    (net (code "52") (name "Net-(DD11-C1+)") (class "Default")
      (node (ref "C72") (pin "1") (pinfunction "1_1") (pintype "passive"))
      (node (ref "DD11") (pin "9") (pinfunction "C1+_9") (pintype "passive"))
    )
    (net (code "53") (name "Net-(DD11-C1-)") (class "Default")
      (node (ref "C72") (pin "2") (pinfunction "2_2") (pintype "passive"))
      (node (ref "DD11") (pin "2") (pinfunction "C1-_2") (pintype "passive"))
    )
    (net (code "54") (name "Net-(DD11-ROUT)") (class "Default")
      (node (ref "DD11") (pin "5") (pinfunction "ROUT_5") (pintype "passive"))
      (node (ref "DD12") (pin "7") (pinfunction "VIA_7") (pintype "passive"))
    )
    (net (code "55") (name "Net-(DD11-TIN)") (class "Default")
      (node (ref "DD11") (pin "4") (pinfunction "TIN_4") (pintype "passive"))
      (node (ref "DD12") (pin "6") (pinfunction "VOB_6") (pintype "passive"))
    )
    (net (code "56") (name "Net-(DD11-V-)") (class "Default")
      (node (ref "C70") (pin "1") (pinfunction "1_1") (pintype "passive"))
      (node (ref "DD11") (pin "3") (pinfunction "V-_3") (pintype "passive"))
    )
    (net (code "57") (name "Net-(DD13-VIA)") (class "Default")
      (node (ref "DD13") (pin "3") (pinfunction "VIA_3") (pintype "passive"))
      (node (ref "R68") (pin "2") (pinfunction "2_2") (pintype "passive"))
      (node (ref "VD7") (pin "1") (pinfunction "K_1") (pintype "passive"))
    )
    (net (code "58") (name "Net-(DD13-VIB)") (class "Default")
      (node (ref "DD13") (pin "4") (pinfunction "VIB_4") (pintype "passive"))
      (node (ref "R62") (pin "2") (pinfunction "2_2") (pintype "passive"))
      (node (ref "VD6") (pin "1") (pinfunction "K_1") (pintype "passive"))
    )
    (net (code "59") (name "Net-(DD13-VIC)") (class "Default")
      (node (ref "DD13") (pin "5") (pinfunction "VIC_5") (pintype "passive"))
      (node (ref "R69") (pin "2") (pinfunction "2_2") (pintype "passive"))
      (node (ref "VD5") (pin "1") (pinfunction "K_1") (pintype "passive"))
    )
    (net (code "60") (name "Net-(DD13-VID)") (class "Default")
      (node (ref "DD13") (pin "6") (pinfunction "VID_6") (pintype "passive"))
      (node (ref "R63") (pin "2") (pinfunction "2_2") (pintype "passive"))
      (node (ref "VD4") (pin "1") (pinfunction "K_1") (pintype "passive"))
    )
    (net (code "61") (name "Net-(DD14-VO)") (class "Default")
      (node (ref "DD14") (pin "6") (pinfunction "VO_6") (pintype "passive"))
      (node (ref "R82") (pin "1") (pinfunction "1_1") (pintype "passive"))
    )
    (net (code "62") (name "Net-(R64-Pad2)") (class "Default")
      (node (ref "R64") (pin "2") (pinfunction "2_2") (pintype "passive"))
      (node (ref "U8") (pin "1") (pintype "passive"))
    )
    (net (code "63") (name "Net-(R65-Pad2)") (class "Default")
      (node (ref "R65") (pin "2") (pinfunction "2_2") (pintype "passive"))
      (node (ref "U8") (pin "3") (pintype "passive"))
    )
    (net (code "64") (name "Net-(R66-Pad2)") (class "Default")
      (node (ref "R66") (pin "2") (pinfunction "2_2") (pintype "passive"))
      (node (ref "U8") (pin "5") (pintype "passive"))
    )
    (net (code "65") (name "Net-(R67-Pad2)") (class "Default")
      (node (ref "R67") (pin "2") (pinfunction "2_2") (pintype "passive"))
      (node (ref "U8") (pin "7") (pintype "passive"))
    )
    (net (code "66") (name "Net-(R70-Pad2)") (class "Default")
      (node (ref "R70") (pin "2") (pinfunction "2_2") (pintype "passive"))
      (node (ref "U9") (pin "2") (pintype "passive"))
    )
    (net (code "67") (name "Net-(R78-Pad1)") (class "Default")
      (node (ref "R78") (pin "1") (pinfunction "1_1") (pintype "passive"))
      (node (ref "U10") (pin "1") (pintype "passive"))
    )
    (net (code "68") (name "Net-(R79-Pad1)") (class "Default")
      (node (ref "R79") (pin "1") (pinfunction "1_1") (pintype "passive"))
      (node (ref "U10") (pin "3") (pintype "passive"))
    )
    (net (code "69") (name "Net-(R80-Pad1)") (class "Default")
      (node (ref "R80") (pin "1") (pinfunction "1_1") (pintype "passive"))
      (node (ref "U10") (pin "5") (pintype "passive"))
    )
    (net (code "70") (name "Net-(R81-Pad1)") (class "Default")
      (node (ref "R81") (pin "1") (pinfunction "1_1") (pintype "passive"))
      (node (ref "U10") (pin "7") (pintype "passive"))
    )
    (net (code "71") (name "unconnected-(DA12-NC-Pad5)") (class "Default")
      (node (ref "DA12") (pin "5") (pinfunction "NC_5") (pintype "passive"))
    )
    (net (code "72") (name "unconnected-(DA12-NC-Pad8)") (class "Default")
      (node (ref "DA12") (pin "8") (pinfunction "NC_8") (pintype "passive"))
    )
    (net (code "73") (name "unconnected-(DA12-ON{slash}OFF-Pad3)") (class "Default")
      (node (ref "DA12") (pin "3") (pinfunction "ON/OFF_3") (pintype "passive"))
    )
    (net (code "74") (name "unconnected-(DD13-NC-Pad7)") (class "Default")
      (node (ref "DD13") (pin "7") (pinfunction "NC_7") (pintype "passive"))
    )
    (net (code "75") (name "unconnected-(U9-Pad7)") (class "Default")
      (node (ref "U9") (pin "7") (pintype "passive"))
    )
    (net (code "76") (name "unconnected-(U9-Pad8)") (class "Default")
      (node (ref "U9") (pin "8") (pintype "passive"))
    )
  )
)
